# truSDX-TCXO-Upgrade-RevB.net
KiCad netlist of a schematic drawn in EAGLE
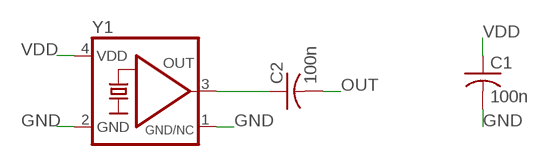
[diagram p0: schematic, sheet 1]

(export (version "E")
  (design (tool "Eeschema 10.0.6"))
  (components
    (comp (ref "C1")
      (value "100n")
      (footprint "eagle-import:C0603")
      (libsource (lib "eagle-import") (part "C-USC0603"))
    )
    (comp (ref "C2")
      (value "100n")
      (footprint "eagle-import:C0603")
      (libsource (lib "eagle-import") (part "C-USC0603"))
    )
    (comp (ref "Y1")
      (value "KXO-TCXO-CMOS-84")
      (footprint "eagle-import:3.2X2.5_KXO-84-TCXO")
      (libsource (lib "eagle-import") (part "KXO-TCXO-CMOS-84"))
    )
  )
  (nets
    (net (code "1") (name "/GND") (class "Default")
      (node (ref "C1") (pin "2") (pinfunction "2_2") (pintype "passive"))
      (node (ref "Y1") (pin "1") (pinfunction "GND/NC_1") (pintype "power_in"))
      (node (ref "Y1") (pin "2") (pinfunction "GND_2") (pintype "power_in"))
    )
    (net (code "2") (name "/OUT") (class "Default")
      (node (ref "C2") (pin "2") (pinfunction "2_2") (pintype "passive"))
    )
    (net (code "3") (name "/VDD") (class "Default")
      (node (ref "C1") (pin "1") (pinfunction "1_1") (pintype "passive"))
      (node (ref "Y1") (pin "4") (pinfunction "VDD_4") (pintype "power_in"))
    )
    (net (code "4") (name "Net-(Y1-OUT)") (class "Default")
      (node (ref "C2") (pin "1") (pinfunction "1_1") (pintype "passive"))
      (node (ref "Y1") (pin "3") (pinfunction "OUT_3") (pintype "output"))
    )
  )
)
